# MCU.net
KiCad netlist of a schematic drawn in Altium Designer
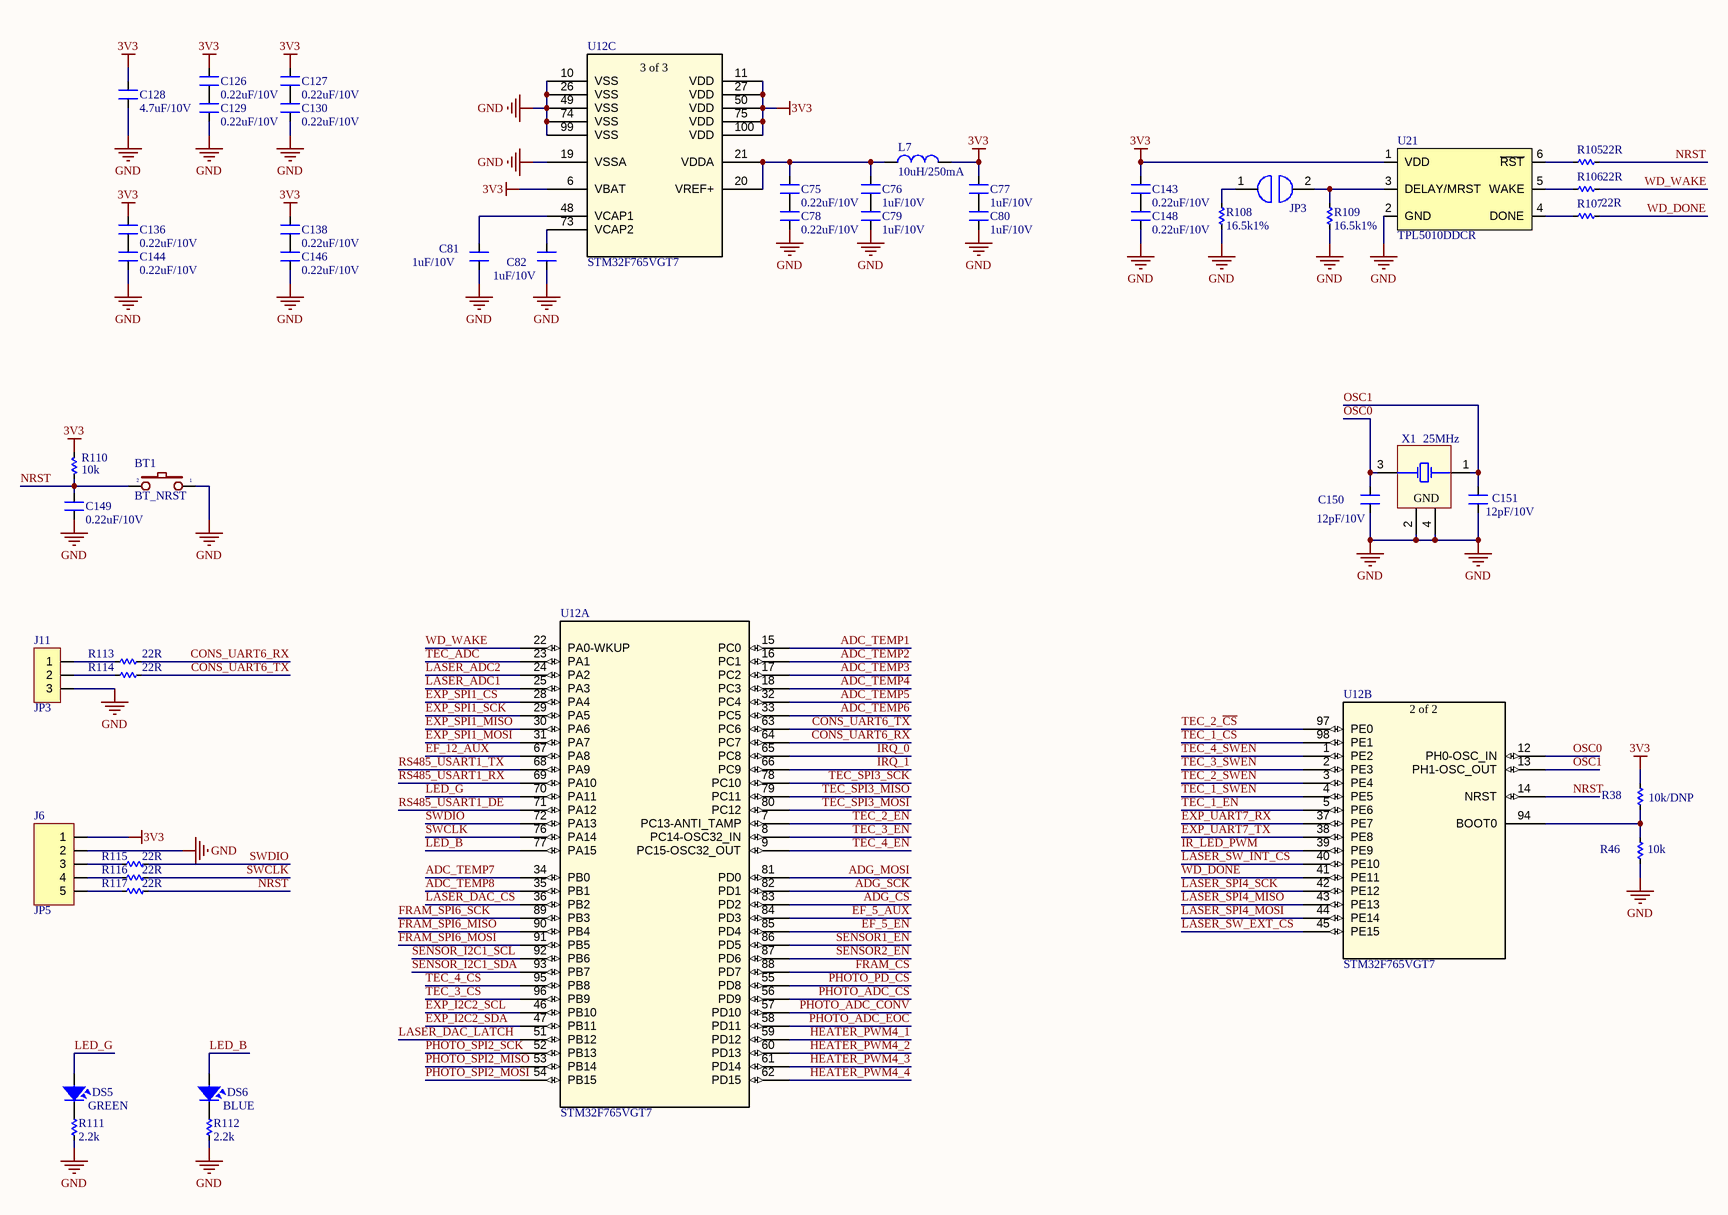
[diagram p0: MCU.SchDoc]

(export (version "E")
  (design (tool "Eeschema 10.0.6"))
  (components
    (comp (ref "BT1")
      (value "BT_NRST")
      (footprint "SW1-SMD")
      (description "Switch button 2 pin")
      (libsource (lib "EXP_HW_V3") (part "SW2"))
    )
    (comp (ref "C75")
      (value "0.22uF/10V")
      (footprint "CAP_C_1608X80")
      (libsource (lib "EXP_HW_V3") (part "Capacitors"))
    )
    (comp (ref "C76")
      (value "1uF/10V")
      (footprint "CAP_C_1608X80")
      (libsource (lib "EXP_HW_V3") (part "Capacitors"))
    )
    (comp (ref "C77")
      (value "1uF/10V")
      (footprint "CAP_C_1608X80")
      (libsource (lib "EXP_HW_V3") (part "Capacitors"))
    )
    (comp (ref "C78")
      (value "0.22uF/10V")
      (footprint "CAP_C_1608X80")
      (libsource (lib "EXP_HW_V3") (part "Capacitors"))
    )
    (comp (ref "C79")
      (value "1uF/10V")
      (footprint "CAP_C_1608X80")
      (libsource (lib "EXP_HW_V3") (part "Capacitors"))
    )
    (comp (ref "C80")
      (value "1uF/10V")
      (footprint "CAP_C_1608X80")
      (libsource (lib "EXP_HW_V3") (part "Capacitors"))
    )
    (comp (ref "C81")
      (value "1uF/10V")
      (footprint "CAP_C_1608X80")
      (libsource (lib "EXP_HW_V3") (part "Capacitors"))
    )
    (comp (ref "C82")
      (value "1uF/10V")
      (footprint "CAP_C_1608X80")
      (libsource (lib "EXP_HW_V3") (part "Capacitors"))
    )
    (comp (ref "C126")
      (value "0.22uF/10V")
      (footprint "CAP_C_1608X80")
      (libsource (lib "EXP_HW_V3") (part "Capacitors"))
    )
    (comp (ref "C127")
      (value "0.22uF/10V")
      (footprint "CAP_C_1608X80")
      (libsource (lib "EXP_HW_V3") (part "Capacitors"))
    )
    (comp (ref "C128")
      (value "4.7uF/10V")
      (footprint "CAP_C_1608X80")
      (libsource (lib "EXP_HW_V3") (part "Capacitors"))
    )
    (comp (ref "C129")
      (value "0.22uF/10V")
      (footprint "CAP_C_1608X80")
      (libsource (lib "EXP_HW_V3") (part "Capacitors"))
    )
    (comp (ref "C130")
      (value "0.22uF/10V")
      (footprint "CAP_C_1608X80")
      (libsource (lib "EXP_HW_V3") (part "Capacitors"))
    )
    (comp (ref "C136")
      (value "0.22uF/10V")
      (footprint "CAP_C_1608X80")
      (libsource (lib "EXP_HW_V3") (part "Capacitors"))
    )
    (comp (ref "C138")
      (value "0.22uF/10V")
      (footprint "CAP_C_1608X80")
      (libsource (lib "EXP_HW_V3") (part "Capacitors"))
    )
    (comp (ref "C143")
      (value "0.22uF/10V")
      (footprint "CAP_C_1608X80")
      (libsource (lib "EXP_HW_V3") (part "Capacitors"))
    )
    (comp (ref "C144")
      (value "0.22uF/10V")
      (footprint "CAP_C_1608X80")
      (libsource (lib "EXP_HW_V3") (part "Capacitors"))
    )
    (comp (ref "C146")
      (value "0.22uF/10V")
      (footprint "CAP_C_1608X80")
      (libsource (lib "EXP_HW_V3") (part "Capacitors"))
    )
    (comp (ref "C148")
      (value "0.22uF/10V")
      (footprint "CAP_C_1608X80")
      (libsource (lib "EXP_HW_V3") (part "Capacitors"))
    )
    (comp (ref "C149")
      (value "0.22uF/10V")
      (footprint "CAP_C_1608X80")
      (libsource (lib "EXP_HW_V3") (part "Capacitors"))
    )
    (comp (ref "C150")
      (value "12pF/10V")
      (footprint "CAP_C_1608X80")
      (libsource (lib "EXP_HW_V3") (part "Capacitors"))
    )
    (comp (ref "C151")
      (value "12pF/10V")
      (footprint "CAP_C_1608X80")
      (libsource (lib "EXP_HW_V3") (part "Capacitors"))
    )
    (comp (ref "DS5")
      (value "GREEN")
      (footprint "LED-0603-BLUE")
      (libsource (lib "EXP_HW_V3") (part "LED SMD"))
    )
    (comp (ref "DS6")
      (value "BLUE")
      (footprint "LED-0603-BLUE")
      (libsource (lib "EXP_HW_V3") (part "LED SMD"))
    )
    (comp (ref "J6")
      (value "JP5")
      (footprint "JP5-D1C")
      (description "WR-PHD 2.54 mm Angled Socket Header")
      (fields
        (field (name "MANUFACTURER") "Würth Elektronik eiSos GmbH")
        (field (name "PARTNO") "613005143121")
        (field (name "CREATED BY") "Karrer Zheng")
      )
      (libsource (lib "EXP_HW_V3") (part "JP5"))
    )
    (comp (ref "J11")
      (value "JP3")
      (footprint "JP3-D1C")
      (description "WR-PHD 2.54 mm Angled Socket Header")
      (fields
        (field (name "MANUFACTURER") "Würth Elektronik eiSos GmbH")
        (field (name "PARTNO") "613003143121")
        (field (name "CREATED BY") "Karrer Zheng")
      )
      (libsource (lib "EXP_HW_V3") (part "JP3"))
    )
    (comp (ref "JP3") (value "jumper2") (footprint "JUMPER2") (libsource (lib "EXP_HW_V3") (part "JUMPER")))
    (comp (ref "L7")
      (value "10uH/250mA")
      (footprint "L-SMD-0603")
      (fields
        (field (name "PARTNO") "78477010")
        (field (name "MANUFACTURER") "Wurth Elektronik")
        (field (name "CREATED BY") "Baojun Chen")
      )
      (libsource (lib "EXP_HW_V3") (part "L-SMD-1"))
    )
    (comp (ref "R38")
      (value "10k/DNP")
      (footprint "RES_C_1608X60")
      (description "SMD")
      (fields
        (field (name "MANUFACTURER") "Generic Components")
        (field (name "PUBLISHER") "Altium Hobart Technology Centre")
      )
      (libsource (lib "EXP_HW_V3") (part "Res SMD"))
    )
    (comp (ref "R46")
      (value "10k")
      (footprint "RES_C_1608X60")
      (description "SMD")
      (fields
        (field (name "MANUFACTURER") "Generic Components")
        (field (name "PUBLISHER") "Altium Hobart Technology Centre")
      )
      (libsource (lib "EXP_HW_V3") (part "Res SMD"))
    )
    (comp (ref "R105")
      (value "22R")
      (footprint "RES_C_1608X60")
      (description "SMD")
      (fields
        (field (name "MANUFACTURER") "Generic Components")
        (field (name "PUBLISHER") "Altium Hobart Technology Centre")
      )
      (libsource (lib "EXP_HW_V3") (part "Res SMD"))
    )
    (comp (ref "R106")
      (value "22R")
      (footprint "RES_C_1608X60")
      (description "SMD")
      (fields
        (field (name "MANUFACTURER") "Generic Components")
        (field (name "PUBLISHER") "Altium Hobart Technology Centre")
      )
      (libsource (lib "EXP_HW_V3") (part "Res SMD"))
    )
    (comp (ref "R107")
      (value "22R")
      (footprint "RES_C_1608X60")
      (description "SMD")
      (fields
        (field (name "MANUFACTURER") "Generic Components")
        (field (name "PUBLISHER") "Altium Hobart Technology Centre")
      )
      (libsource (lib "EXP_HW_V3") (part "Res SMD"))
    )
    (comp (ref "R108")
      (value "16.5k1%")
      (footprint "RES_C_1608X60")
      (description "SMD")
      (fields
        (field (name "MANUFACTURER") "Generic Components")
        (field (name "PUBLISHER") "Altium Hobart Technology Centre")
      )
      (libsource (lib "EXP_HW_V3") (part "Res SMD"))
    )
    (comp (ref "R109")
      (value "16.5k1%")
      (footprint "RES_C_1608X60")
      (description "SMD")
      (fields
        (field (name "MANUFACTURER") "Generic Components")
        (field (name "PUBLISHER") "Altium Hobart Technology Centre")
      )
      (libsource (lib "EXP_HW_V3") (part "Res SMD"))
    )
    (comp (ref "R110")
      (value "10k")
      (footprint "RES_C_1608X60")
      (description "SMD")
      (fields
        (field (name "MANUFACTURER") "Generic Components")
        (field (name "PUBLISHER") "Altium Hobart Technology Centre")
      )
      (libsource (lib "EXP_HW_V3") (part "Res SMD"))
    )
    (comp (ref "R111")
      (value "2.2k")
      (footprint "RES_C_1608X60")
      (description "SMD")
      (fields
        (field (name "MANUFACTURER") "Generic Components")
        (field (name "PUBLISHER") "Altium Hobart Technology Centre")
      )
      (libsource (lib "EXP_HW_V3") (part "Res SMD"))
    )
    (comp (ref "R112")
      (value "2.2k")
      (footprint "RES_C_1608X60")
      (description "SMD")
      (fields
        (field (name "MANUFACTURER") "Generic Components")
        (field (name "PUBLISHER") "Altium Hobart Technology Centre")
      )
      (libsource (lib "EXP_HW_V3") (part "Res SMD"))
    )
    (comp (ref "R113")
      (value "22R")
      (footprint "RES_C_1608X60")
      (description "SMD")
      (fields
        (field (name "MANUFACTURER") "Generic Components")
        (field (name "PUBLISHER") "Altium Hobart Technology Centre")
      )
      (libsource (lib "EXP_HW_V3") (part "Res SMD"))
    )
    (comp (ref "R114")
      (value "22R")
      (footprint "RES_C_1608X60")
      (description "SMD")
      (fields
        (field (name "MANUFACTURER") "Generic Components")
        (field (name "PUBLISHER") "Altium Hobart Technology Centre")
      )
      (libsource (lib "EXP_HW_V3") (part "Res SMD"))
    )
    (comp (ref "R115")
      (value "22R")
      (footprint "RES_C_1608X60")
      (description "SMD")
      (fields
        (field (name "MANUFACTURER") "Generic Components")
        (field (name "PUBLISHER") "Altium Hobart Technology Centre")
      )
      (libsource (lib "EXP_HW_V3") (part "Res SMD"))
    )
    (comp (ref "R116")
      (value "22R")
      (footprint "RES_C_1608X60")
      (description "SMD")
      (fields
        (field (name "MANUFACTURER") "Generic Components")
        (field (name "PUBLISHER") "Altium Hobart Technology Centre")
      )
      (libsource (lib "EXP_HW_V3") (part "Res SMD"))
    )
    (comp (ref "R117")
      (value "22R")
      (footprint "RES_C_1608X60")
      (description "SMD")
      (fields
        (field (name "MANUFACTURER") "Generic Components")
        (field (name "PUBLISHER") "Altium Hobart Technology Centre")
      )
      (libsource (lib "EXP_HW_V3") (part "Res SMD"))
    )
    (comp (ref "U12")
      (value "STM32F765VGT7")
      (footprint "LQFP100_STM")
      (description "No Description Available")
      (libsource (lib "EXP_HW_V3") (part "STM32F765VGT7"))
    )
    (comp (ref "U21")
      (value "TPL5010DDCR")
      (footprint "TPL5010DDCR")
      (description "IC OSC PROG TIMER TSOT23-6")
      (libsource (lib "EXP_HW_V3") (part "TPL5010DDCR"))
    )
    (comp (ref "X1")
      (value "25MHz")
      (footprint "XTAL_ECS-250-12-33Q-JES-TR")
      (description "Crystal, 8 MHz, -30 to 85 degC, 3.2 x 2.5 x 0.9 mm SMD")
      (libsource (lib "Library") (part "XT4"))
    )
  )
  (nets
    (net (code "1") (name "/ADC_TEMP1") (class "Default")
      (node (ref "U12") (pin "15") (pinfunction "PC0_15") (pintype "bidirectional"))
    )
    (net (code "2") (name "/ADC_TEMP2") (class "Default")
      (node (ref "U12") (pin "16") (pinfunction "PC1_16") (pintype "bidirectional"))
    )
    (net (code "3") (name "/ADC_TEMP3") (class "Default")
      (node (ref "U12") (pin "17") (pinfunction "PC2_17") (pintype "bidirectional"))
    )
    (net (code "4") (name "/ADC_TEMP4") (class "Default")
      (node (ref "U12") (pin "18") (pinfunction "PC3_18") (pintype "bidirectional"))
    )
    (net (code "5") (name "/ADC_TEMP5") (class "Default")
      (node (ref "U12") (pin "32") (pinfunction "PC4_32") (pintype "bidirectional"))
    )
    (net (code "6") (name "/ADC_TEMP6") (class "Default")
      (node (ref "U12") (pin "33") (pinfunction "PC5_33") (pintype "bidirectional"))
    )
    (net (code "7") (name "/ADC_TEMP7") (class "Default")
      (node (ref "U12") (pin "34") (pinfunction "PB0_34") (pintype "bidirectional"))
    )
    (net (code "8") (name "/ADC_TEMP8") (class "Default")
      (node (ref "U12") (pin "35") (pinfunction "PB1_35") (pintype "bidirectional"))
    )
    (net (code "9") (name "/ADG_CS") (class "Default")
      (node (ref "U12") (pin "83") (pinfunction "PD2_83") (pintype "bidirectional"))
    )
    (net (code "10") (name "/ADG_MOSI") (class "Default")
      (node (ref "U12") (pin "81") (pinfunction "PD0_81") (pintype "bidirectional"))
    )
    (net (code "11") (name "/ADG_SCK") (class "Default")
      (node (ref "U12") (pin "82") (pinfunction "PD1_82") (pintype "bidirectional"))
    )
    (net (code "12") (name "/CONS_UART6_RX") (class "Default")
      (node (ref "R113") (pin "1") (pinfunction "1_1") (pintype "passive"))
      (node (ref "U12") (pin "64") (pinfunction "PC7_64") (pintype "bidirectional"))
    )
    (net (code "13") (name "/CONS_UART6_TX") (class "Default")
      (node (ref "R114") (pin "1") (pinfunction "1_1") (pintype "passive"))
      (node (ref "U12") (pin "63") (pinfunction "PC6_63") (pintype "bidirectional"))
    )
    (net (code "14") (name "/EF_5_AUX") (class "Default")
      (node (ref "U12") (pin "84") (pinfunction "PD3_84") (pintype "bidirectional"))
    )
    (net (code "15") (name "/EF_5_EN") (class "Default")
      (node (ref "U12") (pin "85") (pinfunction "PD4_85") (pintype "bidirectional"))
    )
    (net (code "16") (name "/EF_12_AUX") (class "Default")
      (node (ref "U12") (pin "67") (pinfunction "PA8_67") (pintype "bidirectional"))
    )
    (net (code "17") (name "/EXP_I2C2_SCL") (class "Default")
      (node (ref "U12") (pin "46") (pinfunction "PB10_46") (pintype "bidirectional"))
    )
    (net (code "18") (name "/EXP_I2C2_SDA") (class "Default")
      (node (ref "U12") (pin "47") (pinfunction "PB11_47") (pintype "bidirectional"))
    )
    (net (code "19") (name "/EXP_SPI1_CS") (class "Default")
      (node (ref "U12") (pin "28") (pinfunction "PA4_28") (pintype "bidirectional"))
    )
    (net (code "20") (name "/EXP_SPI1_MISO") (class "Default")
      (node (ref "U12") (pin "30") (pinfunction "PA6_30") (pintype "bidirectional"))
    )
    (net (code "21") (name "/EXP_SPI1_MOSI") (class "Default")
      (node (ref "U12") (pin "31") (pinfunction "PA7_31") (pintype "bidirectional"))
    )
    (net (code "22") (name "/EXP_SPI1_SCK") (class "Default")
      (node (ref "U12") (pin "29") (pinfunction "PA5_29") (pintype "bidirectional"))
    )
    (net (code "23") (name "/EXP_UART7_RX") (class "Default")
      (node (ref "U12") (pin "37") (pinfunction "PE7_37") (pintype "bidirectional"))
    )
    (net (code "24") (name "/EXP_UART7_TX") (class "Default")
      (node (ref "U12") (pin "38") (pinfunction "PE8_38") (pintype "bidirectional"))
    )
    (net (code "25") (name "/FRAM_CS") (class "Default")
      (node (ref "U12") (pin "88") (pinfunction "PD7_88") (pintype "bidirectional"))
    )
    (net (code "26") (name "/FRAM_SPI6_MISO") (class "Default")
      (node (ref "U12") (pin "90") (pinfunction "PB4_90") (pintype "bidirectional"))
    )
    (net (code "27") (name "/FRAM_SPI6_MOSI") (class "Default")
      (node (ref "U12") (pin "91") (pinfunction "PB5_91") (pintype "bidirectional"))
    )
    (net (code "28") (name "/FRAM_SPI6_SCK") (class "Default")
      (node (ref "U12") (pin "89") (pinfunction "PB3_89") (pintype "bidirectional"))
    )
    (net (code "29") (name "/HEATER_PWM4_1") (class "Default")
      (node (ref "U12") (pin "59") (pinfunction "PD12_59") (pintype "bidirectional"))
    )
    (net (code "30") (name "/HEATER_PWM4_2") (class "Default")
      (node (ref "U12") (pin "60") (pinfunction "PD13_60") (pintype "bidirectional"))
    )
    (net (code "31") (name "/HEATER_PWM4_3") (class "Default")
      (node (ref "U12") (pin "61") (pinfunction "PD14_61") (pintype "bidirectional"))
    )
    (net (code "32") (name "/HEATER_PWM4_4") (class "Default")
      (node (ref "U12") (pin "62") (pinfunction "PD15_62") (pintype "bidirectional"))
    )
    (net (code "33") (name "/IRQ_0") (class "Default")
      (node (ref "U12") (pin "65") (pinfunction "PC8_65") (pintype "bidirectional"))
    )
    (net (code "34") (name "/IRQ_1") (class "Default")
      (node (ref "U12") (pin "66") (pinfunction "PC9_66") (pintype "bidirectional"))
    )
    (net (code "35") (name "/IR_LED_PWM") (class "Default")
      (node (ref "U12") (pin "39") (pinfunction "PE9_39") (pintype "bidirectional"))
    )
    (net (code "36") (name "/LASER_ADC1") (class "Default")
      (node (ref "U12") (pin "25") (pinfunction "PA3_25") (pintype "bidirectional"))
    )
    (net (code "37") (name "/LASER_ADC2") (class "Default")
      (node (ref "U12") (pin "24") (pinfunction "PA2_24") (pintype "bidirectional"))
    )
    (net (code "38") (name "/LASER_DAC_CS") (class "Default")
      (node (ref "U12") (pin "36") (pinfunction "PB2_36") (pintype "bidirectional"))
    )
    (net (code "39") (name "/LASER_DAC_LATCH") (class "Default")
      (node (ref "U12") (pin "51") (pinfunction "PB12_51") (pintype "bidirectional"))
    )
    (net (code "40") (name "/LASER_SPI4_MISO") (class "Default")
      (node (ref "U12") (pin "43") (pinfunction "PE13_43") (pintype "bidirectional"))
    )
    (net (code "41") (name "/LASER_SPI4_MOSI") (class "Default")
      (node (ref "U12") (pin "44") (pinfunction "PE14_44") (pintype "bidirectional"))
    )
    (net (code "42") (name "/LASER_SPI4_SCK") (class "Default")
      (node (ref "U12") (pin "42") (pinfunction "PE12_42") (pintype "bidirectional"))
    )
    (net (code "43") (name "/LASER_SW_EXT_CS") (class "Default")
      (node (ref "U12") (pin "45") (pinfunction "PE15_45") (pintype "bidirectional"))
    )
    (net (code "44") (name "/LASER_SW_INT_CS") (class "Default")
      (node (ref "U12") (pin "40") (pinfunction "PE10_40") (pintype "bidirectional"))
    )
    (net (code "45") (name "/LED_B") (class "Default")
      (node (ref "DS6") (pin "1") (pinfunction "1_1") (pintype "passive"))
      (node (ref "U12") (pin "77") (pinfunction "PA15_77") (pintype "bidirectional"))
    )
    (net (code "46") (name "/LED_G") (class "Default")
      (node (ref "DS5") (pin "1") (pinfunction "1_1") (pintype "passive"))
      (node (ref "U12") (pin "70") (pinfunction "PA11_70") (pintype "bidirectional"))
    )
    (net (code "47") (name "/NRST") (class "Default")
      (node (ref "BT1") (pin "2") (pinfunction "2_2") (pintype "passive"))
      (node (ref "C149") (pin "2") (pinfunction "2_2") (pintype "passive"))
      (node (ref "R105") (pin "2") (pinfunction "2_2") (pintype "passive"))
      (node (ref "R110") (pin "2") (pinfunction "2_2") (pintype "passive"))
      (node (ref "R117") (pin "1") (pinfunction "1_1") (pintype "passive"))
      (node (ref "U12") (pin "14") (pinfunction "NRST_14") (pintype "bidirectional"))
    )
    (net (code "48") (name "/OSC0") (class "Default")
      (node (ref "C150") (pin "1") (pinfunction "1_1") (pintype "passive"))
      (node (ref "U12") (pin "12") (pinfunction "PH0-OSC_IN_12") (pintype "bidirectional"))
      (node (ref "X1") (pin "3") (pinfunction "XTAL_3") (pintype "passive"))
    )
    (net (code "49") (name "/OSC1") (class "Default")
      (node (ref "C151") (pin "2") (pinfunction "2_2") (pintype "passive"))
      (node (ref "U12") (pin "13") (pinfunction "PH1-OSC_OUT_13") (pintype "bidirectional"))
      (node (ref "X1") (pin "1") (pinfunction "XTAL_1") (pintype "passive"))
    )
    (net (code "50") (name "/PHOTO_ADC_CONV") (class "Default")
      (node (ref "U12") (pin "57") (pinfunction "PD10_57") (pintype "bidirectional"))
    )
    (net (code "51") (name "/PHOTO_ADC_CS") (class "Default")
      (node (ref "U12") (pin "56") (pinfunction "PD9_56") (pintype "bidirectional"))
    )
    (net (code "52") (name "/PHOTO_ADC_EOC") (class "Default")
      (node (ref "U12") (pin "58") (pinfunction "PD11_58") (pintype "bidirectional"))
    )
    (net (code "53") (name "/PHOTO_PD_CS") (class "Default")
      (node (ref "U12") (pin "55") (pinfunction "PD8_55") (pintype "bidirectional"))
    )
    (net (code "54") (name "/PHOTO_SPI2_MISO") (class "Default")
      (node (ref "U12") (pin "53") (pinfunction "PB14_53") (pintype "bidirectional"))
    )
    (net (code "55") (name "/PHOTO_SPI2_MOSI") (class "Default")
      (node (ref "U12") (pin "54") (pinfunction "PB15_54") (pintype "bidirectional"))
    )
    (net (code "56") (name "/PHOTO_SPI2_SCK") (class "Default")
      (node (ref "U12") (pin "52") (pinfunction "PB13_52") (pintype "bidirectional"))
    )
    (net (code "57") (name "/RS485_USART1_DE") (class "Default")
      (node (ref "U12") (pin "71") (pinfunction "PA12_71") (pintype "bidirectional"))
    )
    (net (code "58") (name "/RS485_USART1_RX") (class "Default")
      (node (ref "U12") (pin "69") (pinfunction "PA10_69") (pintype "bidirectional"))
    )
    (net (code "59") (name "/RS485_USART1_TX") (class "Default")
      (node (ref "U12") (pin "68") (pinfunction "PA9_68") (pintype "bidirectional"))
    )
    (net (code "60") (name "/SENSOR1_EN") (class "Default")
      (node (ref "U12") (pin "86") (pinfunction "PD5_86") (pintype "bidirectional"))
    )
    (net (code "61") (name "/SENSOR2_EN") (class "Default")
      (node (ref "U12") (pin "87") (pinfunction "PD6_87") (pintype "bidirectional"))
    )
    (net (code "62") (name "/SENSOR_I2C1_SCL") (class "Default")
      (node (ref "U12") (pin "92") (pinfunction "PB6_92") (pintype "bidirectional"))
    )
    (net (code "63") (name "/SENSOR_I2C1_SDA") (class "Default")
      (node (ref "U12") (pin "93") (pinfunction "PB7_93") (pintype "bidirectional"))
    )
    (net (code "64") (name "/SWCLK") (class "Default")
      (node (ref "R116") (pin "1") (pinfunction "1_1") (pintype "passive"))
      (node (ref "U12") (pin "76") (pinfunction "PA14_76") (pintype "bidirectional"))
    )
    (net (code "65") (name "/SWDIO") (class "Default")
      (node (ref "R115") (pin "1") (pinfunction "1_1") (pintype "passive"))
      (node (ref "U12") (pin "72") (pinfunction "PA13_72") (pintype "bidirectional"))
    )
    (net (code "66") (name "/TEC_1_EN") (class "Default")
      (node (ref "U12") (pin "5") (pinfunction "PE6_5") (pintype "bidirectional"))
    )
    (net (code "67") (name "/TEC_1_SWEN") (class "Default")
      (node (ref "U12") (pin "4") (pinfunction "PE5_4") (pintype "bidirectional"))
    )
    (net (code "68") (name "/TEC_1_~{CS}") (class "Default")
      (node (ref "U12") (pin "98") (pinfunction "PE1_98") (pintype "bidirectional"))
    )
    (net (code "69") (name "/TEC_2_EN") (class "Default")
      (node (ref "U12") (pin "7") (pinfunction "PC13-ANTI_TAMP_7") (pintype "bidirectional"))
    )
    (net (code "70") (name "/TEC_2_SWEN") (class "Default")
      (node (ref "U12") (pin "3") (pinfunction "PE4_3") (pintype "bidirectional"))
    )
    (net (code "71") (name "/TEC_2_~{CS}") (class "Default")
      (node (ref "U12") (pin "97") (pinfunction "PE0_97") (pintype "bidirectional"))
    )
    (net (code "72") (name "/TEC_3_EN") (class "Default")
      (node (ref "U12") (pin "8") (pinfunction "PC14-OSC32_IN_8") (pintype "bidirectional"))
    )
    (net (code "73") (name "/TEC_3_SWEN") (class "Default")
      (node (ref "U12") (pin "2") (pinfunction "PE3_2") (pintype "bidirectional"))
    )
    (net (code "74") (name "/TEC_3_~{CS}") (class "Default")
      (node (ref "U12") (pin "96") (pinfunction "PB9_96") (pintype "bidirectional"))
    )
    (net (code "75") (name "/TEC_4_EN") (class "Default")
      (node (ref "U12") (pin "9") (pinfunction "PC15-OSC32_OUT_9") (pintype "bidirectional"))
    )
    (net (code "76") (name "/TEC_4_SWEN") (class "Default")
      (node (ref "U12") (pin "1") (pinfunction "PE2_1") (pintype "bidirectional"))
    )
    (net (code "77") (name "/TEC_4_~{CS}") (class "Default")
      (node (ref "U12") (pin "95") (pinfunction "PB8_95") (pintype "bidirectional"))
    )
    (net (code "78") (name "/TEC_ADC") (class "Default")
      (node (ref "U12") (pin "23") (pinfunction "PA1_23") (pintype "bidirectional"))
    )
    (net (code "79") (name "/TEC_SPI3_MISO") (class "Default")
      (node (ref "U12") (pin "79") (pinfunction "PC11_79") (pintype "bidirectional"))
    )
    (net (code "80") (name "/TEC_SPI3_MOSI") (class "Default")
      (node (ref "U12") (pin "80") (pinfunction "PC12_80") (pintype "bidirectional"))
    )
    (net (code "81") (name "/TEC_SPI3_SCK") (class "Default")
      (node (ref "U12") (pin "78") (pinfunction "PC10_78") (pintype "bidirectional"))
    )
    (net (code "82") (name "/WD_DONE") (class "Default")
      (node (ref "R107") (pin "2") (pinfunction "2_2") (pintype "passive"))
      (node (ref "U12") (pin "41") (pinfunction "PE11_41") (pintype "bidirectional"))
    )
    (net (code "83") (name "/WD_WAKE") (class "Default")
      (node (ref "R106") (pin "2") (pinfunction "2_2") (pintype "passive"))
      (node (ref "U12") (pin "22") (pinfunction "PA0-WKUP_22") (pintype "bidirectional"))
    )
    (net (code "84") (name "3V3") (class "Default")
      (node (ref "C126") (pin "2") (pinfunction "2_2") (pintype "passive"))
      (node (ref "C127") (pin "2") (pinfunction "2_2") (pintype "passive"))
      (node (ref "C128") (pin "2") (pinfunction "2_2") (pintype "passive"))
      (node (ref "C136") (pin "2") (pinfunction "2_2") (pintype "passive"))
      (node (ref "C138") (pin "2") (pinfunction "2_2") (pintype "passive"))
      (node (ref "C143") (pin "2") (pinfunction "2_2") (pintype "passive"))
      (node (ref "C77") (pin "2") (pinfunction "2_2") (pintype "passive"))
      (node (ref "J6") (pin "1") (pinfunction "1_1") (pintype "passive"))
      (node (ref "L7") (pin "1") (pinfunction "1_1") (pintype "passive"))
      (node (ref "R110") (pin "1") (pinfunction "1_1") (pintype "passive"))
      (node (ref "R38") (pin "1") (pinfunction "1_1") (pintype "passive"))
      (node (ref "U12") (pin "100") (pinfunction "VDD_100") (pintype "power_in"))
      (node (ref "U12") (pin "11") (pinfunction "VDD_11") (pintype "power_in"))
      (node (ref "U12") (pin "27") (pinfunction "VDD_27") (pintype "power_in"))
      (node (ref "U12") (pin "50") (pinfunction "VDD_50") (pintype "power_in"))
      (node (ref "U12") (pin "6") (pinfunction "VBAT_6") (pintype "power_in"))
      (node (ref "U12") (pin "75") (pinfunction "VDD_75") (pintype "power_in"))
      (node (ref "U21") (pin "1") (pinfunction "VDD_1") (pintype "passive"))
    )
    (net (code "85") (name "GND") (class "Default")
      (node (ref "BT1") (pin "1") (pinfunction "1_1") (pintype "passive"))
      (node (ref "C128") (pin "1") (pinfunction "1_1") (pintype "passive"))
      (node (ref "C129") (pin "1") (pinfunction "1_1") (pintype "passive"))
      (node (ref "C130") (pin "1") (pinfunction "1_1") (pintype "passive"))
      (node (ref "C144") (pin "1") (pinfunction "1_1") (pintype "passive"))
      (node (ref "C146") (pin "1") (pinfunction "1_1") (pintype "passive"))
      (node (ref "C148") (pin "1") (pinfunction "1_1") (pintype "passive"))
      (node (ref "C149") (pin "1") (pinfunction "1_1") (pintype "passive"))
      (node (ref "C150") (pin "2") (pinfunction "2_2") (pintype "passive"))
      (node (ref "C151") (pin "1") (pinfunction "1_1") (pintype "passive"))
      (node (ref "C78") (pin "1") (pinfunction "1_1") (pintype "passive"))
      (node (ref "C79") (pin "1") (pinfunction "1_1") (pintype "passive"))
      (node (ref "C80") (pin "1") (pinfunction "1_1") (pintype "passive"))
      (node (ref "C81") (pin "1") (pinfunction "1_1") (pintype "passive"))
      (node (ref "C82") (pin "1") (pinfunction "1_1") (pintype "passive"))
      (node (ref "J11") (pin "3") (pinfunction "3_3") (pintype "passive"))
      (node (ref "J6") (pin "2") (pinfunction "2_2") (pintype "passive"))
      (node (ref "R108") (pin "1") (pinfunction "1_1") (pintype "passive"))
      (node (ref "R109") (pin "1") (pinfunction "1_1") (pintype "passive"))
      (node (ref "R111") (pin "2") (pinfunction "2_2") (pintype "passive"))
      (node (ref "R112") (pin "2") (pinfunction "2_2") (pintype "passive"))
      (node (ref "R46") (pin "2") (pinfunction "2_2") (pintype "passive"))
      (node (ref "U12") (pin "10") (pinfunction "VSS_10") (pintype "power_in"))
      (node (ref "U12") (pin "19") (pinfunction "VSSA_19") (pintype "power_in"))
      (node (ref "U12") (pin "26") (pinfunction "VSS_26") (pintype "power_in"))
      (node (ref "U12") (pin "49") (pinfunction "VSS_49") (pintype "power_in"))
      (node (ref "U12") (pin "74") (pinfunction "VSS_74") (pintype "power_in"))
      (node (ref "U12") (pin "99") (pinfunction "VSS_99") (pintype "power_in"))
      (node (ref "U21") (pin "2") (pinfunction "GND_2") (pintype "passive"))
      (node (ref "X1") (pin "2") (pinfunction "GND_2") (pintype "power_in"))
      (node (ref "X1") (pin "4") (pinfunction "GND_4") (pintype "power_in"))
    )
    (net (code "86") (name "Net-(C75-Pad1)") (class "Default")
      (node (ref "C75") (pin "1") (pinfunction "1_1") (pintype "passive"))
      (node (ref "C78") (pin "2") (pinfunction "2_2") (pintype "passive"))
    )
    (net (code "87") (name "Net-(C76-Pad1)") (class "Default")
      (node (ref "C76") (pin "1") (pinfunction "1_1") (pintype "passive"))
      (node (ref "C79") (pin "2") (pinfunction "2_2") (pintype "passive"))
    )
    (net (code "88") (name "Net-(C77-Pad1)") (class "Default")
      (node (ref "C77") (pin "1") (pinfunction "1_1") (pintype "passive"))
      (node (ref "C80") (pin "2") (pinfunction "2_2") (pintype "passive"))
    )
    (net (code "89") (name "Net-(C126-Pad1)") (class "Default")
      (node (ref "C126") (pin "1") (pinfunction "1_1") (pintype "passive"))
      (node (ref "C129") (pin "2") (pinfunction "2_2") (pintype "passive"))
    )
    (net (code "90") (name "Net-(C127-Pad1)") (class "Default")
      (node (ref "C127") (pin "1") (pinfunction "1_1") (pintype "passive"))
      (node (ref "C130") (pin "2") (pinfunction "2_2") (pintype "passive"))
    )
    (net (code "91") (name "Net-(C136-Pad1)") (class "Default")
      (node (ref "C136") (pin "1") (pinfunction "1_1") (pintype "passive"))
      (node (ref "C144") (pin "2") (pinfunction "2_2") (pintype "passive"))
    )
    (net (code "92") (name "Net-(C138-Pad1)") (class "Default")
      (node (ref "C138") (pin "1") (pinfunction "1_1") (pintype "passive"))
      (node (ref "C146") (pin "2") (pinfunction "2_2") (pintype "passive"))
    )
    (net (code "93") (name "Net-(C143-Pad1)") (class "Default")
      (node (ref "C143") (pin "1") (pinfunction "1_1") (pintype "passive"))
      (node (ref "C148") (pin "2") (pinfunction "2_2") (pintype "passive"))
    )
    (net (code "94") (name "Net-(DS5-Pad2)") (class "Default")
      (node (ref "DS5") (pin "2") (pinfunction "2_2") (pintype "passive"))
      (node (ref "R111") (pin "1") (pinfunction "1_1") (pintype "passive"))
    )
    (net (code "95") (name "Net-(DS6-Pad2)") (class "Default")
      (node (ref "DS6") (pin "2") (pinfunction "2_2") (pintype "passive"))
      (node (ref "R112") (pin "1") (pinfunction "1_1") (pintype "passive"))
    )
    (net (code "96") (name "Net-(J6-Pad3)") (class "Default")
      (node (ref "J6") (pin "3") (pinfunction "3_3") (pintype "passive"))
      (node (ref "R115") (pin "2") (pinfunction "2_2") (pintype "passive"))
    )
    (net (code "97") (name "Net-(J6-Pad4)") (class "Default")
      (node (ref "J6") (pin "4") (pinfunction "4_4") (pintype "passive"))
      (node (ref "R116") (pin "2") (pinfunction "2_2") (pintype "passive"))
    )
    (net (code "98") (name "Net-(J6-Pad5)") (class "Default")
      (node (ref "J6") (pin "5") (pinfunction "5_5") (pintype "passive"))
      (node (ref "R117") (pin "2") (pinfunction "2_2") (pintype "passive"))
    )
    (net (code "99") (name "Net-(J11-Pad1)") (class "Default")
      (node (ref "J11") (pin "1") (pinfunction "1_1") (pintype "passive"))
      (node (ref "R113") (pin "2") (pinfunction "2_2") (pintype "passive"))
    )
    (net (code "100") (name "Net-(J11-Pad2)") (class "Default")
      (node (ref "J11") (pin "2") (pinfunction "2_2") (pintype "passive"))
      (node (ref "R114") (pin "2") (pinfunction "2_2") (pintype "passive"))
    )
    (net (code "101") (name "Net-(JP3-Pad1)") (class "Default")
      (node (ref "JP3") (pin "1") (pinfunction "1_1") (pintype "passive"))
      (node (ref "R108") (pin "2") (pinfunction "2_2") (pintype "passive"))
    )
    (net (code "102") (name "Net-(U12B-BOOT0)") (class "Default")
      (node (ref "R38") (pin "2") (pinfunction "2_2") (pintype "passive"))
      (node (ref "R46") (pin "1") (pinfunction "1_1") (pintype "passive"))
      (node (ref "U12") (pin "94") (pinfunction "BOOT0_94") (pintype "input"))
    )
    (net (code "103") (name "Net-(U12C-VCAP1)") (class "Default")
      (node (ref "C81") (pin "2") (pinfunction "2_2") (pintype "passive"))
      (node (ref "U12") (pin "48") (pinfunction "VCAP1_48") (pintype "power_in"))
    )
    (net (code "104") (name "Net-(U12C-VCAP2)") (class "Default")
      (node (ref "C82") (pin "2") (pinfunction "2_2") (pintype "passive"))
      (node (ref "U12") (pin "73") (pinfunction "VCAP2_73") (pintype "power_in"))
    )
    (net (code "105") (name "Net-(U12C-VDDA)") (class "Default")
      (node (ref "C75") (pin "2") (pinfunction "2_2") (pintype "passive"))
      (node (ref "C76") (pin "2") (pinfunction "2_2") (pintype "passive"))
      (node (ref "L7") (pin "2") (pinfunction "2_2") (pintype "passive"))
      (node (ref "U12") (pin "20") (pinfunction "VREF+_20") (pintype "power_in"))
      (node (ref "U12") (pin "21") (pinfunction "VDDA_21") (pintype "power_in"))
    )
    (net (code "106") (name "Net-(U21-DELAY{slash}MRST)") (class "Default")
      (node (ref "JP3") (pin "2") (pinfunction "2_2") (pintype "passive"))
      (node (ref "R109") (pin "2") (pinfunction "2_2") (pintype "passive"))
      (node (ref "U21") (pin "3") (pinfunction "DELAY/MRST_3") (pintype "passive"))
    )
    (net (code "107") (name "Net-(U21-DONE)") (class "Default")
      (node (ref "R107") (pin "1") (pinfunction "1_1") (pintype "passive"))
      (node (ref "U21") (pin "4") (pinfunction "DONE_4") (pintype "passive"))
    )
    (net (code "108") (name "Net-(U21-WAKE)") (class "Default")
      (node (ref "R106") (pin "1") (pinfunction "1_1") (pintype "passive"))
      (node (ref "U21") (pin "5") (pinfunction "WAKE_5") (pintype "passive"))
    )
    (net (code "109") (name "Net-(U21-~{RST})") (class "Default")
      (node (ref "R105") (pin "1") (pinfunction "1_1") (pintype "passive"))
      (node (ref "U21") (pin "6") (pinfunction "~{RST}_6") (pintype "passive"))
    )
  )
)
